# working.net
KiCad netlist of a schematic drawn in EAGLE
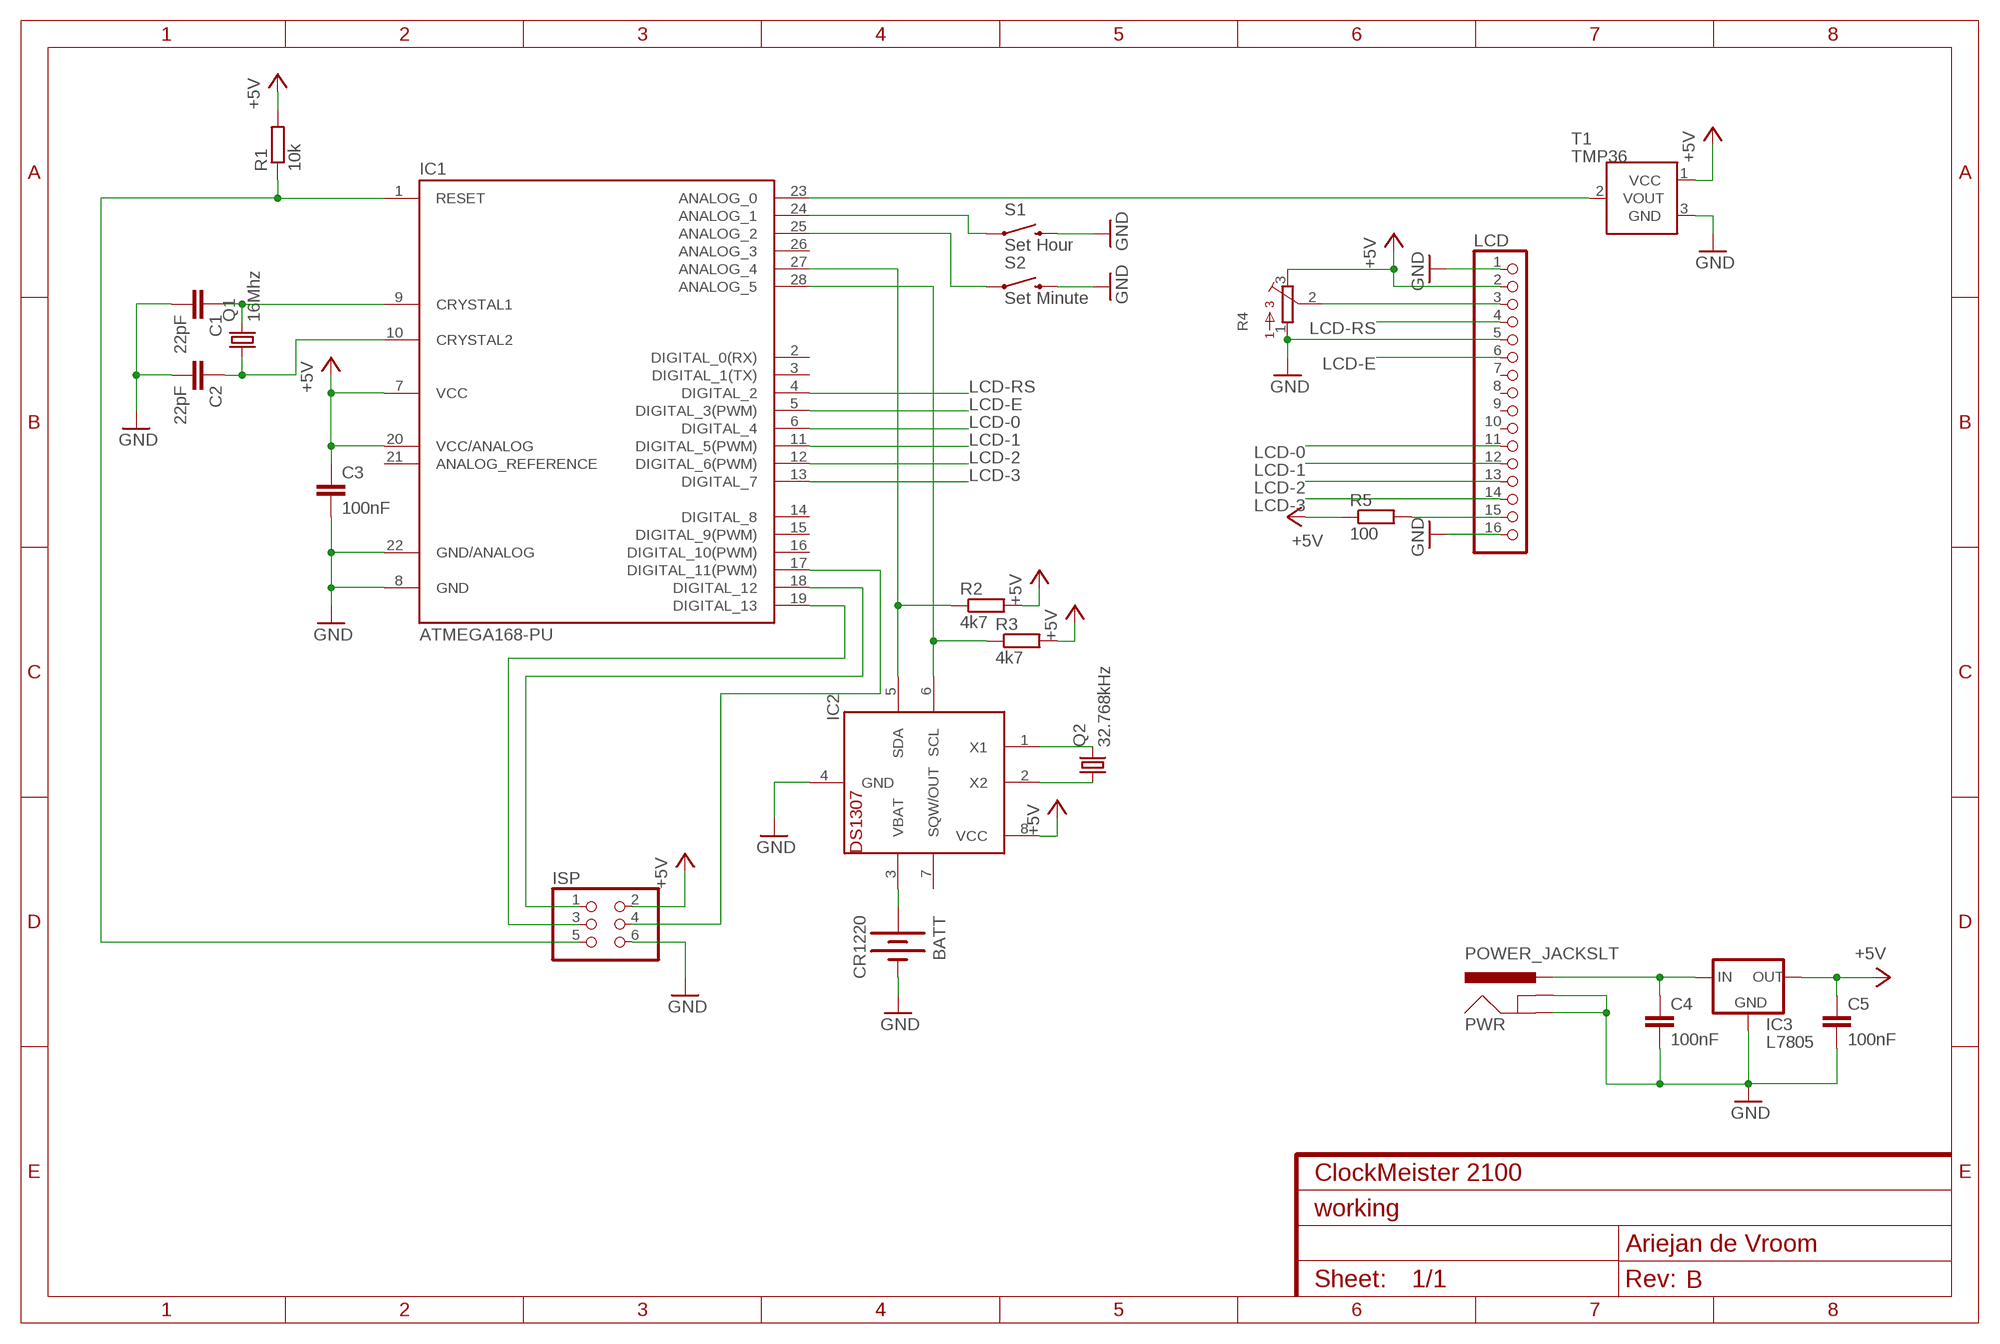
[diagram p0: schematic, sheet 1]

(export (version "E")
  (design (tool "Eeschema 10.0.6"))
  (components
    (comp (ref "BATT")
      (value "CR1220")
      (footprint "eagle-import:BATTCON_12MM_PTH")
      (fields (field (name "MF") "KEYSTONE") (field (name "MPN") "3001"))
      (libsource (lib "eagle-import") (part "BATTERY12PTH"))
    )
    (comp (ref "C1")
      (value "22pF")
      (footprint "eagle-import:C025-025X050")
      (fields (field (name "MF") "MULTICOMP") (field (name "MPN") "MCCHU5220J5"))
      (libsource (lib "eagle-import") (part "C-EU025-025X050"))
    )
    (comp (ref "C2")
      (value "22pF")
      (footprint "eagle-import:C025-025X050")
      (fields (field (name "MF") "MULTICOMP") (field (name "MPN") "MCCHU5220J5"))
      (libsource (lib "eagle-import") (part "C-EU025-025X050"))
    )
    (comp (ref "C3")
      (value "100nF")
      (footprint "eagle-import:C025-025X050")
      (fields (field (name "MF") "MULTICOMP") (field (name "MPN") "MCFYU6104Z6"))
      (libsource (lib "eagle-import") (part "C-EU025-025X050"))
    )
    (comp (ref "C4")
      (value "100nF")
      (footprint "eagle-import:C025-025X050")
      (fields (field (name "MF") "MULTICOMP") (field (name "MPN") "MCFYU6104Z6"))
      (libsource (lib "eagle-import") (part "C-EU025-025X050"))
    )
    (comp (ref "C5")
      (value "100nF")
      (footprint "eagle-import:C025-025X050")
      (fields (field (name "MF") "MULTICOMP") (field (name "MPN") "MCFYU6104Z6"))
      (libsource (lib "eagle-import") (part "C-EU025-025X050"))
    )
    (comp (ref "IC1")
      (value "ATMEGA168-PU")
      (footprint "eagle-import:DIL28-3")
      (fields (field (name "MF") "ATMEL") (field (name "MPN") "ATMEGA328P-PU"))
      (libsource (lib "eagle-import") (part "ATMEGA168-PU"))
    )
    (comp (ref "IC2")
      (value "DS1307")
      (footprint "eagle-import:DIL08")
      (fields (field (name "MF") "MAXIM INTEGRATED PRODUCTS") (field (name "MPN") "DS1307+."))
      (libsource (lib "eagle-import") (part "DS1307"))
    )
    (comp (ref "IC3")
      (value "L7805")
      (footprint "eagle-import:78XXS")
      (fields (field (name "MF") "STMICROELECTRONICS") (field (name "MPN") "L7805CV"))
      (libsource (lib "eagle-import") (part "78XXS"))
    )
    (comp (ref "ISP")
      (value "PINHD-2X3")
      (footprint "eagle-import:2X03")
      (fields (field (name "MF") "TE CONNECTIVITY / AMP") (field (name "MPN") "826942-3"))
      (libsource (lib "eagle-import") (part "PINHD-2X3"))
    )
    (comp (ref "LCD")
      (value "PINHD-1X16")
      (footprint "eagle-import:1X16")
      (fields (field (name "MF") "SAMTEC") (field (name "MPN") "BBS-116-T-A"))
      (libsource (lib "eagle-import") (part "PINHD-1X16"))
    )
    (comp (ref "PWR")
      (value "POWER_JACKSLT")
      (footprint "eagle-import:POWER_JACK_SLOT")
      (libsource (lib "eagle-import") (part "POWER_JACKSLT"))
    )
    (comp (ref "Q1")
      (value "16Mhz")
      (footprint "eagle-import:HC49_S")
      (fields (field (name "MF") "MULTICOMP") (field (name "MPN") "HC49SM-3.6864-30-50-60-16-ATF"))
      (libsource (lib "eagle-import") (part "CRYSTALHC49S"))
    )
    (comp (ref "Q2")
      (value "32.768kHz")
      (footprint "eagle-import:TC26H")
      (fields
        (field (name "MF") "ABRACON")
        (field (name "MPN") "AB38T-32.768KHZ")
        (field (name "OC_FARNELL") "1611828")
      )
      (libsource (lib "eagle-import") (part "CRYSTALTC26H"))
    )
    (comp (ref "R1")
      (value "10k")
      (footprint "eagle-import:0207_10")
      (fields (field (name "MF") "MULTICOMP") (field (name "MPN") "MCCFR0W4J0103A50"))
      (libsource (lib "eagle-import") (part "R-EU_0207/10"))
    )
    (comp (ref "R2")
      (value "4k7")
      (footprint "eagle-import:0207_10")
      (fields (field (name "MF") "MULTICOMP") (field (name "MPN") "MCF 0.5W 4K7"))
      (libsource (lib "eagle-import") (part "R-EU_0207/10"))
    )
    (comp (ref "R3")
      (value "4k7")
      (footprint "eagle-import:0207_10")
      (fields (field (name "MF") "MULTICOMP") (field (name "MPN") "MCF 0.5W 4K7"))
      (libsource (lib "eagle-import") (part "R-EU_0207/10"))
    )
    (comp (ref "R4")
      (value "3386-F")
      (footprint "eagle-import:3386F")
      (libsource (lib "eagle-import") (part "3386-F"))
    )
    (comp (ref "R5")
      (value "100")
      (footprint "eagle-import:0207_10")
      (fields (field (name "MF") "MULTICOMP") (field (name "MPN") "MCCFR0W4J0101A50"))
      (libsource (lib "eagle-import") (part "R-EU_0207/10"))
    )
    (comp (ref "S1")
      (value "Set Hour")
      (footprint "eagle-import:TACTILE-PTH")
      (fields (field (name "MF") "OMRON ELECTRONIC COMPONENTS") (field (name "MPN") "B3F1120"))
      (libsource (lib "eagle-import") (part "SWITCH-MOMENTARY-2PTH"))
    )
    (comp (ref "S2")
      (value "Set Minute")
      (footprint "eagle-import:TACTILE-PTH")
      (fields (field (name "MF") "OMRON ELECTRONIC COMPONENTS") (field (name "MPN") "B3F1120"))
      (libsource (lib "eagle-import") (part "SWITCH-MOMENTARY-2PTH"))
    )
    (comp (ref "T1")
      (value "TMP36")
      (footprint "eagle-import:TO92")
      (libsource (lib "eagle-import") (part "TMP36"))
    )
  )
  (nets
    (net (code "1") (name "+5V") (class "Default")
      (node (ref "C3") (pin "1") (pinfunction "1_1") (pintype "passive"))
      (node (ref "C5") (pin "1") (pinfunction "1_1") (pintype "passive"))
      (node (ref "IC1") (pin "20") (pinfunction "VCC/ANALOG_20") (pintype "passive"))
      (node (ref "IC1") (pin "7") (pinfunction "VCC_7") (pintype "power_in"))
      (node (ref "IC2") (pin "8") (pinfunction "VCC_8") (pintype "power_in"))
      (node (ref "IC3") (pin "OUT") (pinfunction "OUT_OUT") (pintype "passive"))
      (node (ref "ISP") (pin "2") (pinfunction "2_2") (pintype "passive"))
      (node (ref "LCD") (pin "2") (pinfunction "2_2") (pintype "passive"))
      (node (ref "R1") (pin "2") (pinfunction "2_2") (pintype "passive"))
      (node (ref "R2") (pin "2") (pinfunction "2_2") (pintype "passive"))
      (node (ref "R3") (pin "2") (pinfunction "2_2") (pintype "passive"))
      (node (ref "R4") (pin "3") (pinfunction "3_3") (pintype "passive"))
      (node (ref "R5") (pin "1") (pinfunction "1_1") (pintype "passive"))
      (node (ref "T1") (pin "1") (pinfunction "VCC_1") (pintype "power_in"))
    )
    (net (code "2") (name "/LCD-0") (class "Default")
      (node (ref "IC1") (pin "6") (pinfunction "DIGITAL_4_6") (pintype "bidirectional"))
      (node (ref "LCD") (pin "11") (pinfunction "11_11") (pintype "passive"))
    )
    (net (code "3") (name "/LCD-1") (class "Default")
      (node (ref "IC1") (pin "11") (pinfunction "DIGITAL_5(PWM)_11") (pintype "bidirectional"))
      (node (ref "LCD") (pin "12") (pinfunction "12_12") (pintype "passive"))
    )
    (net (code "4") (name "/LCD-2") (class "Default")
      (node (ref "IC1") (pin "12") (pinfunction "DIGITAL_6(PWM)_12") (pintype "bidirectional"))
      (node (ref "LCD") (pin "13") (pinfunction "13_13") (pintype "passive"))
    )
    (net (code "5") (name "/LCD-3") (class "Default")
      (node (ref "IC1") (pin "13") (pinfunction "DIGITAL_7_13") (pintype "bidirectional"))
      (node (ref "LCD") (pin "14") (pinfunction "14_14") (pintype "passive"))
    )
    (net (code "6") (name "/LCD-E") (class "Default")
      (node (ref "IC1") (pin "5") (pinfunction "DIGITAL_3(PWM)_5") (pintype "bidirectional"))
      (node (ref "LCD") (pin "6") (pinfunction "6_6") (pintype "passive"))
    )
    (net (code "7") (name "/LCD-RS") (class "Default")
      (node (ref "IC1") (pin "4") (pinfunction "DIGITAL_2_4") (pintype "bidirectional"))
      (node (ref "LCD") (pin "4") (pinfunction "4_4") (pintype "passive"))
    )
    (net (code "8") (name "GND") (class "Default")
      (node (ref "BATT") (pin "GND") (pinfunction "-_GND") (pintype "power_in"))
      (node (ref "C1") (pin "2") (pinfunction "2_2") (pintype "passive"))
      (node (ref "C2") (pin "2") (pinfunction "2_2") (pintype "passive"))
      (node (ref "C3") (pin "2") (pinfunction "2_2") (pintype "passive"))
      (node (ref "C4") (pin "2") (pinfunction "2_2") (pintype "passive"))
      (node (ref "C5") (pin "2") (pinfunction "2_2") (pintype "passive"))
      (node (ref "IC1") (pin "22") (pinfunction "GND/ANALOG_22") (pintype "power_in"))
      (node (ref "IC1") (pin "8") (pinfunction "GND_8") (pintype "power_in"))
      (node (ref "IC2") (pin "4") (pinfunction "GND_4") (pintype "power_in"))
      (node (ref "IC3") (pin "GND") (pinfunction "GND_GND") (pintype "input"))
      (node (ref "ISP") (pin "6") (pinfunction "6_6") (pintype "passive"))
      (node (ref "LCD") (pin "1") (pinfunction "1_1") (pintype "passive"))
      (node (ref "LCD") (pin "16") (pinfunction "16_16") (pintype "passive"))
      (node (ref "LCD") (pin "5") (pinfunction "5_5") (pintype "passive"))
      (node (ref "PWR") (pin "GND@1") (pinfunction "GNDBREAK_GND@1") (pintype "bidirectional"))
      (node (ref "PWR") (pin "GND@2") (pinfunction "GND_GND@2") (pintype "bidirectional"))
      (node (ref "R4") (pin "1") (pinfunction "1_1") (pintype "passive"))
      (node (ref "S1") (pin "3") (pinfunction "2_3") (pintype "passive"))
      (node (ref "S2") (pin "3") (pinfunction "2_3") (pintype "passive"))
      (node (ref "T1") (pin "3") (pinfunction "GND_3") (pintype "power_in"))
    )
    (net (code "9") (name "Net-(BATT-+)") (class "Default")
      (node (ref "BATT") (pin "VCC@1") (pinfunction "+_VCC@1") (pintype "power_in"))
      (node (ref "IC2") (pin "3") (pinfunction "VBAT_3") (pintype "power_in"))
    )
    (net (code "10") (name "Net-(C4-Pad1)") (class "Default")
      (node (ref "C4") (pin "1") (pinfunction "1_1") (pintype "passive"))
      (node (ref "IC3") (pin "IN") (pinfunction "IN_IN") (pintype "input"))
      (node (ref "PWR") (pin "PWR") (pinfunction "PWR_PWR") (pintype "bidirectional"))
    )
    (net (code "11") (name "Net-(IC1-ANALOG_0)") (class "Default")
      (node (ref "IC1") (pin "23") (pinfunction "ANALOG_0_23") (pintype "bidirectional"))
      (node (ref "T1") (pin "2") (pinfunction "VOUT_2") (pintype "output"))
    )
    (net (code "12") (name "Net-(IC1-ANALOG_1)") (class "Default")
      (node (ref "IC1") (pin "24") (pinfunction "ANALOG_1_24") (pintype "bidirectional"))
      (node (ref "S1") (pin "1") (pinfunction "1_1") (pintype "passive"))
    )
    (net (code "13") (name "Net-(IC1-ANALOG_2)") (class "Default")
      (node (ref "IC1") (pin "25") (pinfunction "ANALOG_2_25") (pintype "bidirectional"))
      (node (ref "S2") (pin "1") (pinfunction "1_1") (pintype "passive"))
    )
    (net (code "14") (name "Net-(IC1-ANALOG_4)") (class "Default")
      (node (ref "IC1") (pin "27") (pinfunction "ANALOG_4_27") (pintype "bidirectional"))
      (node (ref "IC2") (pin "5") (pinfunction "SDA_5") (pintype "bidirectional"))
      (node (ref "R2") (pin "1") (pinfunction "1_1") (pintype "passive"))
    )
    (net (code "15") (name "Net-(IC1-ANALOG_5)") (class "Default")
      (node (ref "IC1") (pin "28") (pinfunction "ANALOG_5_28") (pintype "bidirectional"))
      (node (ref "IC2") (pin "6") (pinfunction "SCL_6") (pintype "bidirectional"))
      (node (ref "R3") (pin "1") (pinfunction "1_1") (pintype "passive"))
    )
    (net (code "16") (name "Net-(IC1-CRYSTAL1)") (class "Default")
      (node (ref "C1") (pin "1") (pinfunction "1_1") (pintype "passive"))
      (node (ref "IC1") (pin "9") (pinfunction "CRYSTAL1_9") (pintype "bidirectional"))
      (node (ref "Q1") (pin "2") (pinfunction "2_2") (pintype "passive"))
    )
    (net (code "17") (name "Net-(IC1-CRYSTAL2)") (class "Default")
      (node (ref "C2") (pin "1") (pinfunction "1_1") (pintype "passive"))
      (node (ref "IC1") (pin "10") (pinfunction "CRYSTAL2_10") (pintype "bidirectional"))
      (node (ref "Q1") (pin "1") (pinfunction "1_1") (pintype "passive"))
    )
    (net (code "18") (name "Net-(IC1-DIGITAL_11(PWM))") (class "Default")
      (node (ref "IC1") (pin "17") (pinfunction "DIGITAL_11(PWM)_17") (pintype "bidirectional"))
      (node (ref "ISP") (pin "4") (pinfunction "4_4") (pintype "passive"))
    )
    (net (code "19") (name "Net-(IC1-DIGITAL_12)") (class "Default")
      (node (ref "IC1") (pin "18") (pinfunction "DIGITAL_12_18") (pintype "bidirectional"))
      (node (ref "ISP") (pin "1") (pinfunction "1_1") (pintype "passive"))
    )
    (net (code "20") (name "Net-(IC1-DIGITAL_13)") (class "Default")
      (node (ref "IC1") (pin "19") (pinfunction "DIGITAL_13_19") (pintype "bidirectional"))
      (node (ref "ISP") (pin "3") (pinfunction "3_3") (pintype "passive"))
    )
    (net (code "21") (name "Net-(IC1-RESET)") (class "Default")
      (node (ref "IC1") (pin "1") (pinfunction "RESET_1") (pintype "bidirectional"))
      (node (ref "ISP") (pin "5") (pinfunction "5_5") (pintype "passive"))
      (node (ref "R1") (pin "1") (pinfunction "1_1") (pintype "passive"))
    )
    (net (code "22") (name "Net-(IC2-X1)") (class "Default")
      (node (ref "IC2") (pin "1") (pinfunction "X1_1") (pintype "passive"))
      (node (ref "Q2") (pin "2") (pinfunction "2_2") (pintype "passive"))
    )
    (net (code "23") (name "Net-(IC2-X2)") (class "Default")
      (node (ref "IC2") (pin "2") (pinfunction "X2_2") (pintype "passive"))
      (node (ref "Q2") (pin "1") (pinfunction "1_1") (pintype "passive"))
    )
    (net (code "24") (name "Net-(LCD-Pad3)") (class "Default")
      (node (ref "LCD") (pin "3") (pinfunction "3_3") (pintype "passive"))
      (node (ref "R4") (pin "2") (pinfunction "2_2") (pintype "passive"))
    )
    (net (code "25") (name "Net-(LCD-Pad15)") (class "Default")
      (node (ref "LCD") (pin "15") (pinfunction "15_15") (pintype "passive"))
      (node (ref "R5") (pin "2") (pinfunction "2_2") (pintype "passive"))
    )
    (net (code "26") (name "unconnected-(IC1-ANALOG_3-Pad26)") (class "Default")
      (node (ref "IC1") (pin "26") (pinfunction "ANALOG_3_26") (pintype "bidirectional"))
    )
    (net (code "27") (name "unconnected-(IC1-ANALOG_REFERENCE-Pad21)") (class "Default")
      (node (ref "IC1") (pin "21") (pinfunction "ANALOG_REFERENCE_21") (pintype "passive"))
    )
    (net (code "28") (name "unconnected-(IC1-DIGITAL_0(RX)-Pad2)") (class "Default")
      (node (ref "IC1") (pin "2") (pinfunction "DIGITAL_0(RX)_2") (pintype "bidirectional"))
    )
    (net (code "29") (name "unconnected-(IC1-DIGITAL_1(TX)-Pad3)") (class "Default")
      (node (ref "IC1") (pin "3") (pinfunction "DIGITAL_1(TX)_3") (pintype "bidirectional"))
    )
    (net (code "30") (name "unconnected-(IC1-DIGITAL_8-Pad14)") (class "Default")
      (node (ref "IC1") (pin "14") (pinfunction "DIGITAL_8_14") (pintype "bidirectional"))
    )
    (net (code "31") (name "unconnected-(IC1-DIGITAL_9(PWM)-Pad15)") (class "Default")
      (node (ref "IC1") (pin "15") (pinfunction "DIGITAL_9(PWM)_15") (pintype "bidirectional"))
    )
    (net (code "32") (name "unconnected-(IC1-DIGITAL_10(PWM)-Pad16)") (class "Default")
      (node (ref "IC1") (pin "16") (pinfunction "DIGITAL_10(PWM)_16") (pintype "bidirectional"))
    )
    (net (code "33") (name "unconnected-(IC2-SQW{slash}OUT-Pad7)") (class "Default")
      (node (ref "IC2") (pin "7") (pinfunction "SQW/OUT_7") (pintype "bidirectional"))
    )
    (net (code "34") (name "unconnected-(LCD-Pad7)") (class "Default")
      (node (ref "LCD") (pin "7") (pinfunction "7_7") (pintype "passive"))
    )
    (net (code "35") (name "unconnected-(LCD-Pad8)") (class "Default")
      (node (ref "LCD") (pin "8") (pinfunction "8_8") (pintype "passive"))
    )
    (net (code "36") (name "unconnected-(LCD-Pad9)") (class "Default")
      (node (ref "LCD") (pin "9") (pinfunction "9_9") (pintype "passive"))
    )
    (net (code "37") (name "unconnected-(LCD-Pad10)") (class "Default")
      (node (ref "LCD") (pin "10") (pinfunction "10_10") (pintype "passive"))
    )
  )
)
